# Filter-18.net
KiCad netlist of a schematic drawn in Altium Designer
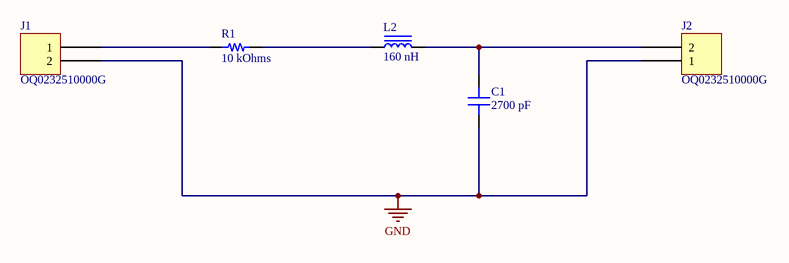
[diagram p0: Filter-18.SchDoc]

(export (version "E")
  (design (tool "Eeschema 10.0.6"))
  (components
    (comp (ref "C1")
      (value "2700 pF")
      (footprint "CAP 0603_1608")
      (description "CAP CER 2700PF 25V NP0 0603")
      (fields (field (name "PART NUMBER") "C0603C272F3GAC7867") (field (name "MANUFACTURER") "KEMET"))
      (libsource (lib "Celestial Altium Library - altium_library") (part "Capacitor"))
    )
    (comp (ref "J1")
      (value "OQ0232510000G")
      (footprint "FCI 06-381-2PIN")
      (description "TERM BLOCK HDR 2POS 90DEG 3.81MM")
      (fields (field (name "MANUFACTURER") "Amphenol Anytek"))
      (libsource (lib "Celestial Altium Library - altium_library") (part "2 Pin"))
    )
    (comp (ref "J2")
      (value "OQ0232510000G")
      (footprint "FCI 06-381-2PIN")
      (description "TERM BLOCK HDR 2POS 90DEG 3.81MM")
      (fields (field (name "MANUFACTURER") "Amphenol Anytek"))
      (libsource (lib "") (part "2 Pin_1"))
    )
    (comp (ref "L2")
      (value "160 nH")
      (footprint "IND 0402_1005 RF WW")
      (description "FIXED IND 160NH 480MA 330MOHM SM")
      (fields
        (field (name "PART NUMBER") "LQW15CNR16J00D")
        (field (name "MANUFACTURER") "Murata Electronics")
      )
      (libsource (lib "Celestial Altium Library - altium_library") (part "Inductor"))
    )
    (comp (ref "R1")
      (value "10 kOhms")
      (footprint "RES 0603_1608")
      (description "RES 10K OHM 0.1% 1/16W 0603")
      (fields
        (field (name "PART NUMBER") "RNCS0603BKE10K0")
        (field (name "MANUFACTURER") "Stackpole Electronics Inc")
      )
      (libsource (lib "Celestial Altium Library - altium_library") (part "Resistor"))
    )
  )
  (nets
    (net (code "1") (name "GND") (class "Default")
      (node (ref "C1") (pin "1") (pinfunction "1_1") (pintype "passive"))
      (node (ref "J1") (pin "2") (pinfunction "2_2") (pintype "passive"))
      (node (ref "J2") (pin "1") (pinfunction "1_1") (pintype "passive"))
    )
    (net (code "2") (name "Net-(C1-Pad2)") (class "Default")
      (node (ref "C1") (pin "2") (pinfunction "2_2") (pintype "passive"))
      (node (ref "J2") (pin "2") (pinfunction "2_2") (pintype "passive"))
      (node (ref "L2") (pin "2") (pinfunction "2_2") (pintype "passive"))
    )
    (net (code "3") (name "Net-(J1-Pad1)") (class "Default")
      (node (ref "J1") (pin "1") (pinfunction "1_1") (pintype "passive"))
      (node (ref "R1") (pin "1") (pinfunction "1_1") (pintype "passive"))
    )
    (net (code "4") (name "Net-(L2-Pad1)") (class "Default")
      (node (ref "L2") (pin "1") (pinfunction "1_1") (pintype "passive"))
      (node (ref "R1") (pin "2") (pinfunction "2_2") (pintype "passive"))
    )
  )
)
